# segment.net
KiCad netlist of a schematic drawn in EAGLE
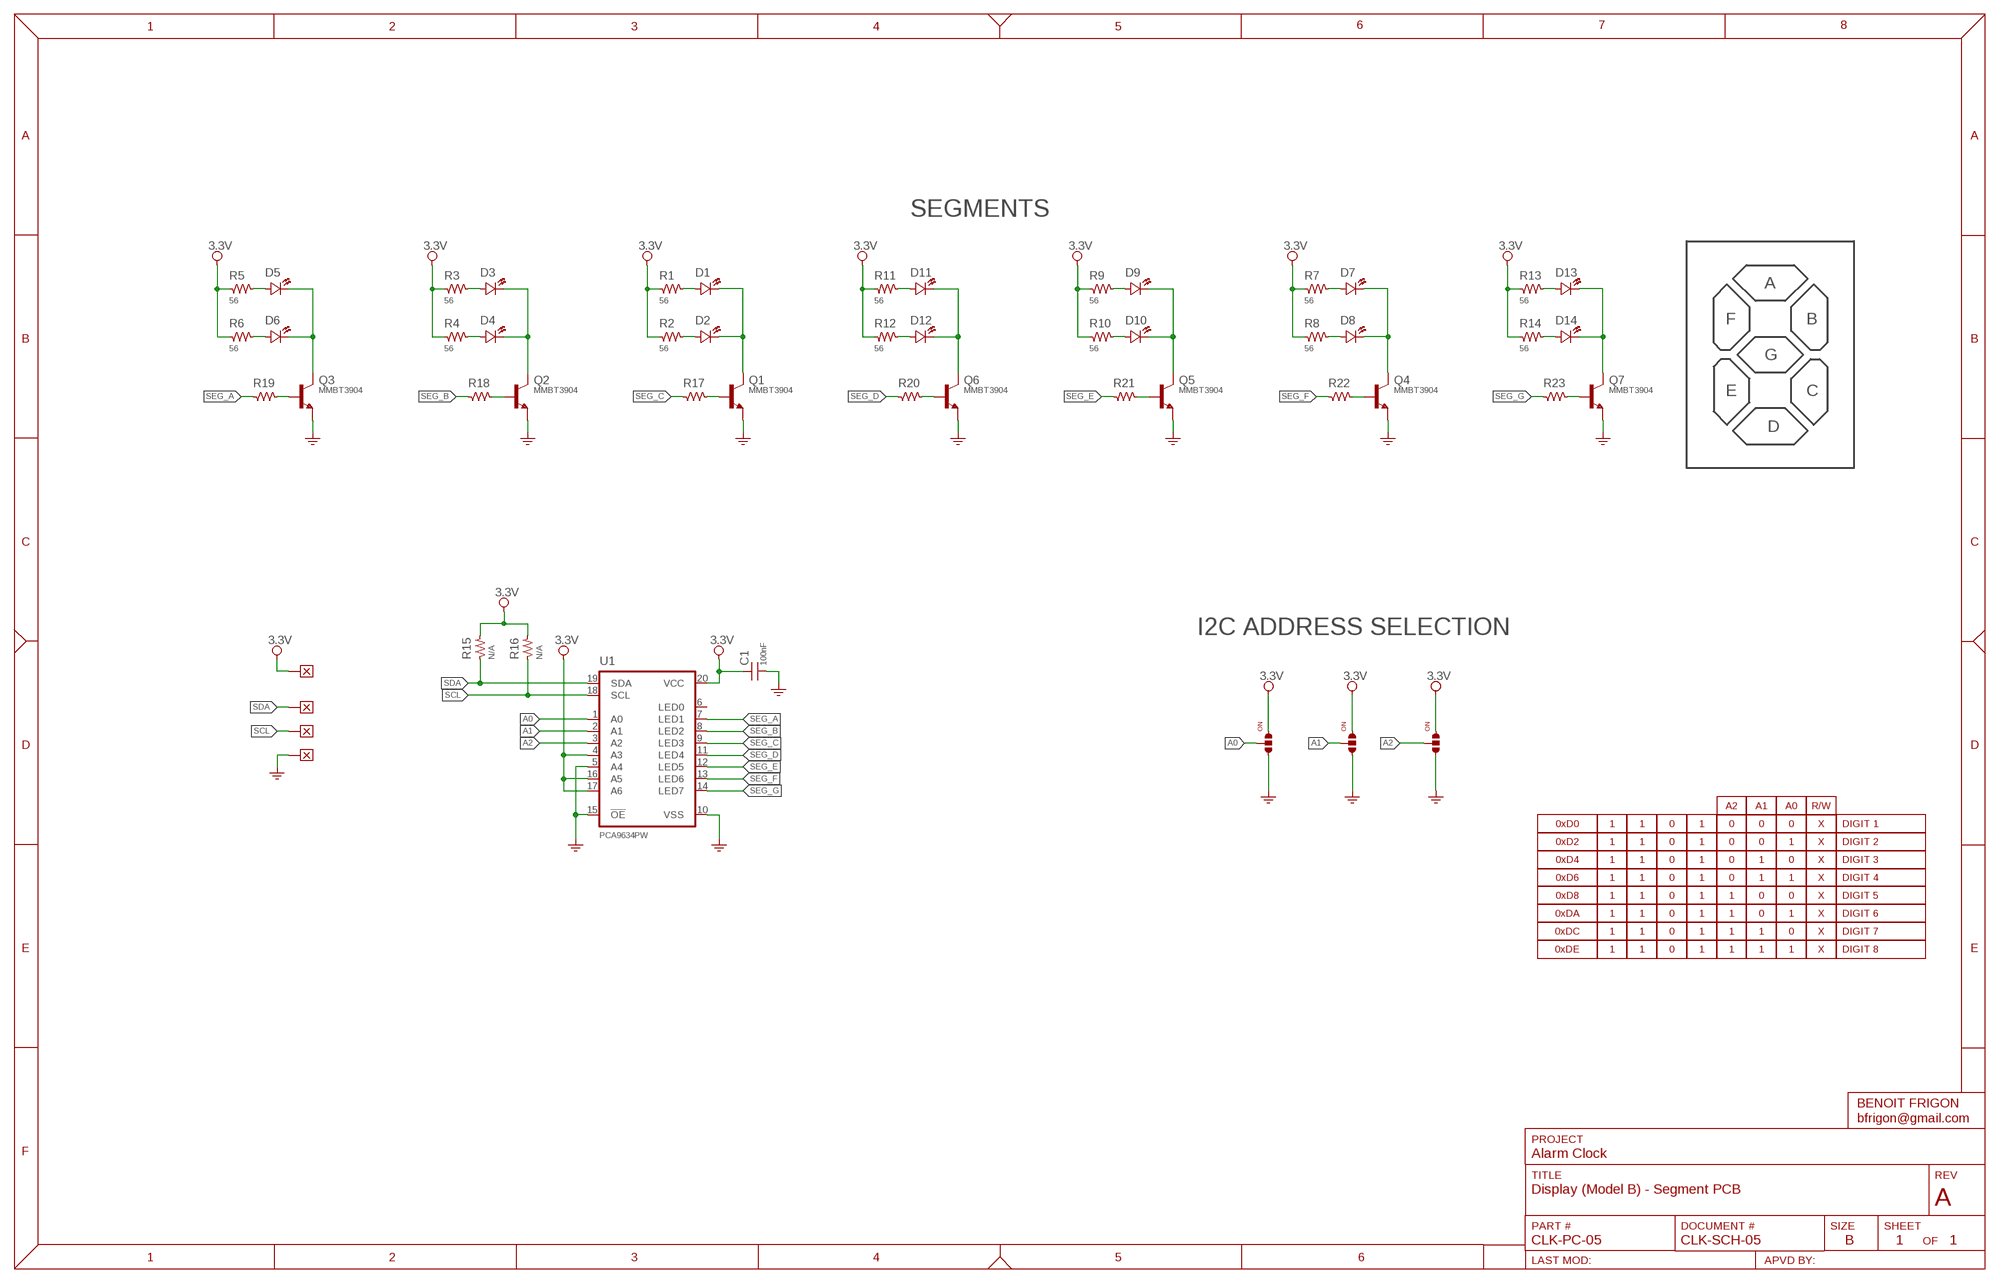
[diagram p0: schematic, sheet 1]

(export (version "E")
  (design (tool "Eeschema 10.0.6"))
  (components
    (comp (ref "C1")
      (value "100nF")
      (footprint "eagle-import:SMD_0603")
      (libsource (lib "eagle-import") (part "CAP-0603"))
    )
    (comp (ref "D1")
      (value "Red")
      (footprint "eagle-import:CHIPLED_0805")
      (fields
        (field (name "COLOR") "Red")
        (field (name "MFG") "Kingbright")
        (field (name "SKU") "APT2012SECK/J3-PRV")
      )
      (libsource (lib "eagle-import") (part "LED-0805"))
    )
    (comp (ref "D2")
      (value "Red")
      (footprint "eagle-import:CHIPLED_0805")
      (fields
        (field (name "COLOR") "Red")
        (field (name "MFG") "Kingbright")
        (field (name "SKU") "APT2012SECK/J3-PRV")
      )
      (libsource (lib "eagle-import") (part "LED-0805"))
    )
    (comp (ref "D3")
      (value "Red")
      (footprint "eagle-import:CHIPLED_0805")
      (fields
        (field (name "COLOR") "Red")
        (field (name "MFG") "Kingbright")
        (field (name "SKU") "APT2012SECK/J3-PRV")
      )
      (libsource (lib "eagle-import") (part "LED-0805"))
    )
    (comp (ref "D4")
      (value "Red")
      (footprint "eagle-import:CHIPLED_0805")
      (description "{DESCRIPTION} Chip 0805 - {ATTR:COLOR}")
      (fields
        (field (name "COLOR") "Red")
        (field (name "MFG") "Kingbright")
        (field (name "PACKAGE") "SMT 0805")
        (field (name "SKU") "APT2012SECK/J3-PRV")
      )
      (libsource (lib "eagle-import") (part "LED-0805"))
    )
    (comp (ref "D5")
      (value "Red")
      (footprint "eagle-import:CHIPLED_0805")
      (description "{DESCRIPTION} Chip 0805 - {ATTR:COLOR}")
      (fields
        (field (name "COLOR") "Red")
        (field (name "MFG") "Kingbright")
        (field (name "PACKAGE") "SMT 0805")
        (field (name "SKU") "APT2012SECK/J3-PRV")
      )
      (libsource (lib "eagle-import") (part "LED-0805"))
    )
    (comp (ref "D6")
      (value "Red")
      (footprint "eagle-import:CHIPLED_0805")
      (description "{DESCRIPTION} Chip 0805 - {ATTR:COLOR}")
      (fields
        (field (name "COLOR") "Red")
        (field (name "MFG") "Kingbright")
        (field (name "PACKAGE") "SMT 0805")
        (field (name "SKU") "APT2012SECK/J3-PRV")
      )
      (libsource (lib "eagle-import") (part "LED-0805"))
    )
    (comp (ref "D7")
      (value "Red")
      (footprint "eagle-import:CHIPLED_0805")
      (fields
        (field (name "COLOR") "Red")
        (field (name "MFG") "Kingbright")
        (field (name "SKU") "APT2012SECK/J3-PRV")
      )
      (libsource (lib "eagle-import") (part "LED-0805"))
    )
    (comp (ref "D8")
      (value "Red")
      (footprint "eagle-import:CHIPLED_0805")
      (fields
        (field (name "COLOR") "Red")
        (field (name "MFG") "Kingbright")
        (field (name "SKU") "APT2012SECK/J3-PRV")
      )
      (libsource (lib "eagle-import") (part "LED-0805"))
    )
    (comp (ref "D9")
      (value "Red")
      (footprint "eagle-import:CHIPLED_0805")
      (fields
        (field (name "COLOR") "Red")
        (field (name "MFG") "Kingbright")
        (field (name "SKU") "APT2012SECK/J3-PRV")
      )
      (libsource (lib "eagle-import") (part "LED-0805"))
    )
    (comp (ref "D10")
      (value "Red")
      (footprint "eagle-import:CHIPLED_0805")
      (fields
        (field (name "COLOR") "Red")
        (field (name "MFG") "Kingbright")
        (field (name "SKU") "APT2012SECK/J3-PRV")
      )
      (libsource (lib "eagle-import") (part "LED-0805"))
    )
    (comp (ref "D11")
      (value "Red")
      (footprint "eagle-import:CHIPLED_0805")
      (description "{DESCRIPTION} Chip 0805 - {ATTR:COLOR}")
      (fields
        (field (name "COLOR") "Red")
        (field (name "MFG") "Kingbright")
        (field (name "PACKAGE") "SMT 0805")
        (field (name "SKU") "APT2012SECK/J3-PRV")
      )
      (libsource (lib "eagle-import") (part "LED-0805"))
    )
    (comp (ref "D12")
      (value "Red")
      (footprint "eagle-import:CHIPLED_0805")
      (description "{DESCRIPTION} Chip 0805 - {ATTR:COLOR}")
      (fields
        (field (name "COLOR") "Red")
        (field (name "MFG") "Kingbright")
        (field (name "PACKAGE") "SMT 0805")
        (field (name "SKU") "APT2012SECK/J3-PRV")
      )
      (libsource (lib "eagle-import") (part "LED-0805"))
    )
    (comp (ref "D13")
      (value "Red")
      (footprint "eagle-import:CHIPLED_0805")
      (description "{DESCRIPTION} Chip 0805 - {ATTR:COLOR}")
      (fields
        (field (name "COLOR") "Red")
        (field (name "MFG") "Kingbright")
        (field (name "PACKAGE") "SMT 0805")
        (field (name "SKU") "APT2012SECK/J3-PRV")
      )
      (libsource (lib "eagle-import") (part "LED-0805"))
    )
    (comp (ref "D14")
      (value "Red")
      (footprint "eagle-import:CHIPLED_0805")
      (description "{DESCRIPTION} Chip 0805 - {ATTR:COLOR}")
      (fields
        (field (name "COLOR") "Red")
        (field (name "MFG") "Kingbright")
        (field (name "PACKAGE") "SMT 0805")
        (field (name "SKU") "APT2012SECK/J3-PRV")
      )
      (libsource (lib "eagle-import") (part "LED-0805"))
    )
    (comp (ref "J1")
      (value "SOLDER_JUMPER_3")
      (footprint "eagle-import:SOLDER_JUMPER_3")
      (libsource (lib "eagle-import") (part "SOLDER_JUMPER_3"))
    )
    (comp (ref "J2")
      (value "SOLDER_JUMPER_3")
      (footprint "eagle-import:SOLDER_JUMPER_3")
      (libsource (lib "eagle-import") (part "SOLDER_JUMPER_3"))
    )
    (comp (ref "J3")
      (value "SOLDER_JUMPER_3")
      (footprint "eagle-import:SOLDER_JUMPER_3")
      (libsource (lib "eagle-import") (part "SOLDER_JUMPER_3"))
    )
    (comp (ref "Q1")
      (value "MMBT3904")
      (footprint "eagle-import:SOT23")
      (libsource (lib "eagle-import") (part "MMBT3904"))
    )
    (comp (ref "Q2")
      (value "MMBT3904")
      (footprint "eagle-import:SOT23")
      (libsource (lib "eagle-import") (part "MMBT3904"))
    )
    (comp (ref "Q3")
      (value "MMBT3904")
      (footprint "eagle-import:SOT23")
      (libsource (lib "eagle-import") (part "MMBT3904"))
    )
    (comp (ref "Q4")
      (value "MMBT3904")
      (footprint "eagle-import:SOT23")
      (libsource (lib "eagle-import") (part "MMBT3904"))
    )
    (comp (ref "Q5")
      (value "MMBT3904")
      (footprint "eagle-import:SOT23")
      (libsource (lib "eagle-import") (part "MMBT3904"))
    )
    (comp (ref "Q6")
      (value "MMBT3904")
      (footprint "eagle-import:SOT23")
      (libsource (lib "eagle-import") (part "MMBT3904"))
    )
    (comp (ref "Q7")
      (value "MMBT3904")
      (footprint "eagle-import:SOT23")
      (libsource (lib "eagle-import") (part "MMBT3904"))
    )
    (comp (ref "R1")
      (value "56")
      (footprint "eagle-import:SMD_0603")
      (libsource (lib "eagle-import") (part "RES-0603"))
    )
    (comp (ref "R2")
      (value "56")
      (footprint "eagle-import:SMD_0603")
      (description "{DESCRIPTION} - SMT 0603 - {VALUE}")
      (fields (field (name "PACKAGE") "SMT 0603"))
      (libsource (lib "eagle-import") (part "RES-0603"))
    )
    (comp (ref "R3")
      (value "56")
      (footprint "eagle-import:SMD_0603")
      (description "{DESCRIPTION} - SMT 0603 - {VALUE}")
      (fields (field (name "PACKAGE") "SMT 0603"))
      (libsource (lib "eagle-import") (part "RES-0603"))
    )
    (comp (ref "R4")
      (value "56")
      (footprint "eagle-import:SMD_0603")
      (description "{DESCRIPTION} - SMT 0603 - {VALUE}")
      (fields (field (name "PACKAGE") "SMT 0603"))
      (libsource (lib "eagle-import") (part "RES-0603"))
    )
    (comp (ref "R5")
      (value "56")
      (footprint "eagle-import:SMD_0603")
      (description "{DESCRIPTION} - SMT 0603 - {VALUE}")
      (fields (field (name "PACKAGE") "SMT 0603"))
      (libsource (lib "eagle-import") (part "RES-0603"))
    )
    (comp (ref "R6")
      (value "56")
      (footprint "eagle-import:SMD_0603")
      (description "{DESCRIPTION} - SMT 0603 - {VALUE}")
      (fields (field (name "PACKAGE") "SMT 0603"))
      (libsource (lib "eagle-import") (part "RES-0603"))
    )
    (comp (ref "R7")
      (value "56")
      (footprint "eagle-import:SMD_0603")
      (description "{DESCRIPTION} - SMT 0603 - {VALUE}")
      (fields (field (name "PACKAGE") "SMT 0603"))
      (libsource (lib "eagle-import") (part "RES-0603"))
    )
    (comp (ref "R8")
      (value "56")
      (footprint "eagle-import:SMD_0603")
      (description "{DESCRIPTION} - SMT 0603 - {VALUE}")
      (fields (field (name "PACKAGE") "SMT 0603"))
      (libsource (lib "eagle-import") (part "RES-0603"))
    )
    (comp (ref "R9")
      (value "56")
      (footprint "eagle-import:SMD_0603")
      (description "{DESCRIPTION} - SMT 0603 - {VALUE}")
      (fields (field (name "PACKAGE") "SMT 0603"))
      (libsource (lib "eagle-import") (part "RES-0603"))
    )
    (comp (ref "R10")
      (value "56")
      (footprint "eagle-import:SMD_0603")
      (description "{DESCRIPTION} - SMT 0603 - {VALUE}")
      (fields (field (name "PACKAGE") "SMT 0603"))
      (libsource (lib "eagle-import") (part "RES-0603"))
    )
    (comp (ref "R11")
      (value "56")
      (footprint "eagle-import:SMD_0603")
      (description "{DESCRIPTION} - SMT 0603 - {VALUE}")
      (fields (field (name "PACKAGE") "SMT 0603"))
      (libsource (lib "eagle-import") (part "RES-0603"))
    )
    (comp (ref "R12")
      (value "56")
      (footprint "eagle-import:SMD_0603")
      (description "{DESCRIPTION} - SMT 0603 - {VALUE}")
      (fields (field (name "PACKAGE") "SMT 0603"))
      (libsource (lib "eagle-import") (part "RES-0603"))
    )
    (comp (ref "R13")
      (value "56")
      (footprint "eagle-import:SMD_0603")
      (description "{DESCRIPTION} - SMT 0603 - {VALUE}")
      (fields (field (name "PACKAGE") "SMT 0603"))
      (libsource (lib "eagle-import") (part "RES-0603"))
    )
    (comp (ref "R14")
      (value "56")
      (footprint "eagle-import:SMD_0603")
      (description "{DESCRIPTION} - SMT 0603 - {VALUE}")
      (fields (field (name "PACKAGE") "SMT 0603"))
      (libsource (lib "eagle-import") (part "RES-0603"))
    )
    (comp (ref "R15")
      (value "N/A")
      (footprint "eagle-import:SMD_0603")
      (libsource (lib "eagle-import") (part "RES-0603"))
    )
    (comp (ref "R16")
      (value "N/A")
      (footprint "eagle-import:SMD_0603")
      (libsource (lib "eagle-import") (part "RES-0603"))
    )
    (comp (ref "R17")
      (value "RES-0603")
      (footprint "eagle-import:SMD_0603")
      (libsource (lib "eagle-import") (part "RES-0603"))
    )
    (comp (ref "R18")
      (value "RES-0603")
      (footprint "eagle-import:SMD_0603")
      (description "{DESCRIPTION} - SMT 0603 - {VALUE}")
      (fields (field (name "PACKAGE") "SMT 0603"))
      (libsource (lib "eagle-import") (part "RES-0603"))
    )
    (comp (ref "R19")
      (value "RES-0603")
      (footprint "eagle-import:SMD_0603")
      (description "{DESCRIPTION} - SMT 0603 - {VALUE}")
      (fields (field (name "PACKAGE") "SMT 0603"))
      (libsource (lib "eagle-import") (part "RES-0603"))
    )
    (comp (ref "R20")
      (value "RES-0603")
      (footprint "eagle-import:SMD_0603")
      (description "{DESCRIPTION} - SMT 0603 - {VALUE}")
      (fields (field (name "PACKAGE") "SMT 0603"))
      (libsource (lib "eagle-import") (part "RES-0603"))
    )
    (comp (ref "R21")
      (value "RES-0603")
      (footprint "eagle-import:SMD_0603")
      (description "{DESCRIPTION} - SMT 0603 - {VALUE}")
      (fields (field (name "PACKAGE") "SMT 0603"))
      (libsource (lib "eagle-import") (part "RES-0603"))
    )
    (comp (ref "R22")
      (value "RES-0603")
      (footprint "eagle-import:SMD_0603")
      (description "{DESCRIPTION} - SMT 0603 - {VALUE}")
      (fields (field (name "PACKAGE") "SMT 0603"))
      (libsource (lib "eagle-import") (part "RES-0603"))
    )
    (comp (ref "R23")
      (value "RES-0603")
      (footprint "eagle-import:SMD_0603")
      (description "{DESCRIPTION} - SMT 0603 - {VALUE}")
      (fields (field (name "PACKAGE") "SMT 0603"))
      (libsource (lib "eagle-import") (part "RES-0603"))
    )
    (comp (ref "U1")
      (value "PCA9634PW")
      (footprint "eagle-import:TSSOP20")
      (fields (field (name "MFG") "NXP Semiconductors"))
      (libsource (lib "eagle-import") (part "PCA9634PW"))
    )
    (comp (ref "W1")
      (value "WIRE")
      (footprint "eagle-import:WIRE_SMT")
      (libsource (lib "eagle-import") (part "WIRE"))
    )
    (comp (ref "W2")
      (value "WIRE")
      (footprint "eagle-import:WIRE_SMT")
      (libsource (lib "eagle-import") (part "WIRE"))
    )
    (comp (ref "W3")
      (value "WIRE")
      (footprint "eagle-import:WIRE_SMT")
      (libsource (lib "eagle-import") (part "WIRE"))
    )
    (comp (ref "W4")
      (value "WIRE")
      (footprint "eagle-import:WIRE_SMT")
      (libsource (lib "eagle-import") (part "WIRE"))
    )
  )
  (nets
    (net (code "1") (name "3.3V") (class "Default")
      (node (ref "C1") (pin "1") (pinfunction "1_1") (pintype "passive"))
      (node (ref "J1") (pin "1") (pinfunction "1_1") (pintype "bidirectional"))
      (node (ref "J2") (pin "1") (pinfunction "1_1") (pintype "bidirectional"))
      (node (ref "J3") (pin "1") (pinfunction "1_1") (pintype "bidirectional"))
      (node (ref "R1") (pin "1") (pinfunction "1_1") (pintype "passive"))
      (node (ref "R10") (pin "1") (pinfunction "1_1") (pintype "passive"))
      (node (ref "R11") (pin "1") (pinfunction "1_1") (pintype "passive"))
      (node (ref "R12") (pin "1") (pinfunction "1_1") (pintype "passive"))
      (node (ref "R13") (pin "1") (pinfunction "1_1") (pintype "passive"))
      (node (ref "R14") (pin "1") (pinfunction "1_1") (pintype "passive"))
      (node (ref "R15") (pin "2") (pinfunction "2_2") (pintype "passive"))
      (node (ref "R16") (pin "2") (pinfunction "2_2") (pintype "passive"))
      (node (ref "R2") (pin "1") (pinfunction "1_1") (pintype "passive"))
      (node (ref "R3") (pin "1") (pinfunction "1_1") (pintype "passive"))
      (node (ref "R4") (pin "1") (pinfunction "1_1") (pintype "passive"))
      (node (ref "R5") (pin "1") (pinfunction "1_1") (pintype "passive"))
      (node (ref "R6") (pin "1") (pinfunction "1_1") (pintype "passive"))
      (node (ref "R7") (pin "1") (pinfunction "1_1") (pintype "passive"))
      (node (ref "R8") (pin "1") (pinfunction "1_1") (pintype "passive"))
      (node (ref "R9") (pin "1") (pinfunction "1_1") (pintype "passive"))
      (node (ref "U1") (pin "16") (pinfunction "A5_16") (pintype "bidirectional"))
      (node (ref "U1") (pin "17") (pinfunction "A6_17") (pintype "bidirectional"))
      (node (ref "U1") (pin "20") (pinfunction "VCC_20") (pintype "bidirectional"))
      (node (ref "U1") (pin "4") (pinfunction "A3_4") (pintype "bidirectional"))
      (node (ref "W1") (pin "1") (pinfunction "P$1_1") (pintype "bidirectional"))
    )
    (net (code "2") (name "A0") (class "Default")
      (node (ref "J2") (pin "2") (pinfunction "2_2") (pintype "bidirectional"))
      (node (ref "U1") (pin "1") (pinfunction "A0_1") (pintype "bidirectional"))
    )
    (net (code "3") (name "A1") (class "Default")
      (node (ref "J1") (pin "2") (pinfunction "2_2") (pintype "bidirectional"))
      (node (ref "U1") (pin "2") (pinfunction "A1_2") (pintype "bidirectional"))
    )
    (net (code "4") (name "A2") (class "Default")
      (node (ref "J3") (pin "2") (pinfunction "2_2") (pintype "bidirectional"))
      (node (ref "U1") (pin "3") (pinfunction "A2_3") (pintype "bidirectional"))
    )
    (net (code "5") (name "GND") (class "Default")
      (node (ref "C1") (pin "2") (pinfunction "2_2") (pintype "passive"))
      (node (ref "J1") (pin "3") (pinfunction "3_3") (pintype "bidirectional"))
      (node (ref "J2") (pin "3") (pinfunction "3_3") (pintype "bidirectional"))
      (node (ref "J3") (pin "3") (pinfunction "3_3") (pintype "bidirectional"))
      (node (ref "Q1") (pin "2") (pinfunction "E_2") (pintype "passive"))
      (node (ref "Q2") (pin "2") (pinfunction "E_2") (pintype "passive"))
      (node (ref "Q3") (pin "2") (pinfunction "E_2") (pintype "passive"))
      (node (ref "Q4") (pin "2") (pinfunction "E_2") (pintype "passive"))
      (node (ref "Q5") (pin "2") (pinfunction "E_2") (pintype "passive"))
      (node (ref "Q6") (pin "2") (pinfunction "E_2") (pintype "passive"))
      (node (ref "Q7") (pin "2") (pinfunction "E_2") (pintype "passive"))
      (node (ref "U1") (pin "10") (pinfunction "VSS_10") (pintype "bidirectional"))
      (node (ref "U1") (pin "15") (pinfunction "~{OE}_15") (pintype "bidirectional"))
      (node (ref "U1") (pin "5") (pinfunction "A4_5") (pintype "bidirectional"))
      (node (ref "W4") (pin "1") (pinfunction "P$1_1") (pintype "bidirectional"))
    )
    (net (code "6") (name "Net-(D1-PadA)") (class "Default")
      (node (ref "D1") (pin "A") (pinfunction "A_A") (pintype "passive"))
      (node (ref "R1") (pin "2") (pinfunction "2_2") (pintype "passive"))
    )
    (net (code "7") (name "Net-(D2-PadA)") (class "Default")
      (node (ref "D2") (pin "A") (pinfunction "A_A") (pintype "passive"))
      (node (ref "R2") (pin "2") (pinfunction "2_2") (pintype "passive"))
    )
    (net (code "8") (name "Net-(D3-PadA)") (class "Default")
      (node (ref "D3") (pin "A") (pinfunction "A_A") (pintype "passive"))
      (node (ref "R3") (pin "2") (pinfunction "2_2") (pintype "passive"))
    )
    (net (code "9") (name "Net-(D4-PadA)") (class "Default")
      (node (ref "D4") (pin "A") (pinfunction "A_A") (pintype "passive"))
      (node (ref "R4") (pin "2") (pinfunction "2_2") (pintype "passive"))
    )
    (net (code "10") (name "Net-(D5-PadA)") (class "Default")
      (node (ref "D5") (pin "A") (pinfunction "A_A") (pintype "passive"))
      (node (ref "R5") (pin "2") (pinfunction "2_2") (pintype "passive"))
    )
    (net (code "11") (name "Net-(D6-PadA)") (class "Default")
      (node (ref "D6") (pin "A") (pinfunction "A_A") (pintype "passive"))
      (node (ref "R6") (pin "2") (pinfunction "2_2") (pintype "passive"))
    )
    (net (code "12") (name "Net-(D7-PadA)") (class "Default")
      (node (ref "D7") (pin "A") (pinfunction "A_A") (pintype "passive"))
      (node (ref "R7") (pin "2") (pinfunction "2_2") (pintype "passive"))
    )
    (net (code "13") (name "Net-(D8-PadA)") (class "Default")
      (node (ref "D8") (pin "A") (pinfunction "A_A") (pintype "passive"))
      (node (ref "R8") (pin "2") (pinfunction "2_2") (pintype "passive"))
    )
    (net (code "14") (name "Net-(D9-PadA)") (class "Default")
      (node (ref "D9") (pin "A") (pinfunction "A_A") (pintype "passive"))
      (node (ref "R9") (pin "2") (pinfunction "2_2") (pintype "passive"))
    )
    (net (code "15") (name "Net-(D10-PadA)") (class "Default")
      (node (ref "D10") (pin "A") (pinfunction "A_A") (pintype "passive"))
      (node (ref "R10") (pin "2") (pinfunction "2_2") (pintype "passive"))
    )
    (net (code "16") (name "Net-(D11-PadA)") (class "Default")
      (node (ref "D11") (pin "A") (pinfunction "A_A") (pintype "passive"))
      (node (ref "R11") (pin "2") (pinfunction "2_2") (pintype "passive"))
    )
    (net (code "17") (name "Net-(D12-PadA)") (class "Default")
      (node (ref "D12") (pin "A") (pinfunction "A_A") (pintype "passive"))
      (node (ref "R12") (pin "2") (pinfunction "2_2") (pintype "passive"))
    )
    (net (code "18") (name "Net-(D13-PadA)") (class "Default")
      (node (ref "D13") (pin "A") (pinfunction "A_A") (pintype "passive"))
      (node (ref "R13") (pin "2") (pinfunction "2_2") (pintype "passive"))
    )
    (net (code "19") (name "Net-(D14-PadA)") (class "Default")
      (node (ref "D14") (pin "A") (pinfunction "A_A") (pintype "passive"))
      (node (ref "R14") (pin "2") (pinfunction "2_2") (pintype "passive"))
    )
    (net (code "20") (name "Net-(Q1-B)") (class "Default")
      (node (ref "Q1") (pin "1") (pinfunction "B_1") (pintype "passive"))
      (node (ref "R17") (pin "2") (pinfunction "2_2") (pintype "passive"))
    )
    (net (code "21") (name "Net-(Q1-C)") (class "Default")
      (node (ref "D1") (pin "K") (pinfunction "K_K") (pintype "passive"))
      (node (ref "D2") (pin "K") (pinfunction "K_K") (pintype "passive"))
      (node (ref "Q1") (pin "3") (pinfunction "C_3") (pintype "passive"))
    )
    (net (code "22") (name "Net-(Q2-B)") (class "Default")
      (node (ref "Q2") (pin "1") (pinfunction "B_1") (pintype "passive"))
      (node (ref "R18") (pin "2") (pinfunction "2_2") (pintype "passive"))
    )
    (net (code "23") (name "Net-(Q2-C)") (class "Default")
      (node (ref "D3") (pin "K") (pinfunction "K_K") (pintype "passive"))
      (node (ref "D4") (pin "K") (pinfunction "K_K") (pintype "passive"))
      (node (ref "Q2") (pin "3") (pinfunction "C_3") (pintype "passive"))
    )
    (net (code "24") (name "Net-(Q3-B)") (class "Default")
      (node (ref "Q3") (pin "1") (pinfunction "B_1") (pintype "passive"))
      (node (ref "R19") (pin "2") (pinfunction "2_2") (pintype "passive"))
    )
    (net (code "25") (name "Net-(Q3-C)") (class "Default")
      (node (ref "D5") (pin "K") (pinfunction "K_K") (pintype "passive"))
      (node (ref "D6") (pin "K") (pinfunction "K_K") (pintype "passive"))
      (node (ref "Q3") (pin "3") (pinfunction "C_3") (pintype "passive"))
    )
    (net (code "26") (name "Net-(Q4-B)") (class "Default")
      (node (ref "Q4") (pin "1") (pinfunction "B_1") (pintype "passive"))
      (node (ref "R22") (pin "2") (pinfunction "2_2") (pintype "passive"))
    )
    (net (code "27") (name "Net-(Q4-C)") (class "Default")
      (node (ref "D7") (pin "K") (pinfunction "K_K") (pintype "passive"))
      (node (ref "D8") (pin "K") (pinfunction "K_K") (pintype "passive"))
      (node (ref "Q4") (pin "3") (pinfunction "C_3") (pintype "passive"))
    )
    (net (code "28") (name "Net-(Q5-B)") (class "Default")
      (node (ref "Q5") (pin "1") (pinfunction "B_1") (pintype "passive"))
      (node (ref "R21") (pin "2") (pinfunction "2_2") (pintype "passive"))
    )
    (net (code "29") (name "Net-(Q5-C)") (class "Default")
      (node (ref "D10") (pin "K") (pinfunction "K_K") (pintype "passive"))
      (node (ref "D9") (pin "K") (pinfunction "K_K") (pintype "passive"))
      (node (ref "Q5") (pin "3") (pinfunction "C_3") (pintype "passive"))
    )
    (net (code "30") (name "Net-(Q6-B)") (class "Default")
      (node (ref "Q6") (pin "1") (pinfunction "B_1") (pintype "passive"))
      (node (ref "R20") (pin "2") (pinfunction "2_2") (pintype "passive"))
    )
    (net (code "31") (name "Net-(Q6-C)") (class "Default")
      (node (ref "D11") (pin "K") (pinfunction "K_K") (pintype "passive"))
      (node (ref "D12") (pin "K") (pinfunction "K_K") (pintype "passive"))
      (node (ref "Q6") (pin "3") (pinfunction "C_3") (pintype "passive"))
    )
    (net (code "32") (name "Net-(Q7-B)") (class "Default")
      (node (ref "Q7") (pin "1") (pinfunction "B_1") (pintype "passive"))
      (node (ref "R23") (pin "2") (pinfunction "2_2") (pintype "passive"))
    )
    (net (code "33") (name "Net-(Q7-C)") (class "Default")
      (node (ref "D13") (pin "K") (pinfunction "K_K") (pintype "passive"))
      (node (ref "D14") (pin "K") (pinfunction "K_K") (pintype "passive"))
      (node (ref "Q7") (pin "3") (pinfunction "C_3") (pintype "passive"))
    )
    (net (code "34") (name "SCL") (class "Default")
      (node (ref "R16") (pin "1") (pinfunction "1_1") (pintype "passive"))
      (node (ref "U1") (pin "18") (pinfunction "SCL_18") (pintype "bidirectional"))
      (node (ref "W3") (pin "1") (pinfunction "P$1_1") (pintype "bidirectional"))
    )
    (net (code "35") (name "SDA") (class "Default")
      (node (ref "R15") (pin "1") (pinfunction "1_1") (pintype "passive"))
      (node (ref "U1") (pin "19") (pinfunction "SDA_19") (pintype "bidirectional"))
      (node (ref "W2") (pin "1") (pinfunction "P$1_1") (pintype "bidirectional"))
    )
    (net (code "36") (name "SEG_A") (class "Default")
      (node (ref "R19") (pin "1") (pinfunction "1_1") (pintype "passive"))
      (node (ref "U1") (pin "7") (pinfunction "LED1_7") (pintype "bidirectional"))
    )
    (net (code "37") (name "SEG_B") (class "Default")
      (node (ref "R18") (pin "1") (pinfunction "1_1") (pintype "passive"))
      (node (ref "U1") (pin "8") (pinfunction "LED2_8") (pintype "bidirectional"))
    )
    (net (code "38") (name "SEG_C") (class "Default")
      (node (ref "R17") (pin "1") (pinfunction "1_1") (pintype "passive"))
      (node (ref "U1") (pin "9") (pinfunction "LED3_9") (pintype "bidirectional"))
    )
    (net (code "39") (name "SEG_D") (class "Default")
      (node (ref "R20") (pin "1") (pinfunction "1_1") (pintype "passive"))
      (node (ref "U1") (pin "11") (pinfunction "LED4_11") (pintype "bidirectional"))
    )
    (net (code "40") (name "SEG_E") (class "Default")
      (node (ref "R21") (pin "1") (pinfunction "1_1") (pintype "passive"))
      (node (ref "U1") (pin "12") (pinfunction "LED5_12") (pintype "bidirectional"))
    )
    (net (code "41") (name "SEG_F") (class "Default")
      (node (ref "R22") (pin "1") (pinfunction "1_1") (pintype "passive"))
      (node (ref "U1") (pin "13") (pinfunction "LED6_13") (pintype "bidirectional"))
    )
    (net (code "42") (name "SEG_G") (class "Default")
      (node (ref "R23") (pin "1") (pinfunction "1_1") (pintype "passive"))
      (node (ref "U1") (pin "14") (pinfunction "LED7_14") (pintype "bidirectional"))
    )
    (net (code "43") (name "unconnected-(U1-LED0-Pad6)") (class "Default")
      (node (ref "U1") (pin "6") (pinfunction "LED0_6") (pintype "bidirectional"))
    )
  )
)
